# 1A19J6_1A20J15_A.net
KiCad netlist of a schematic drawn in Altium Designer
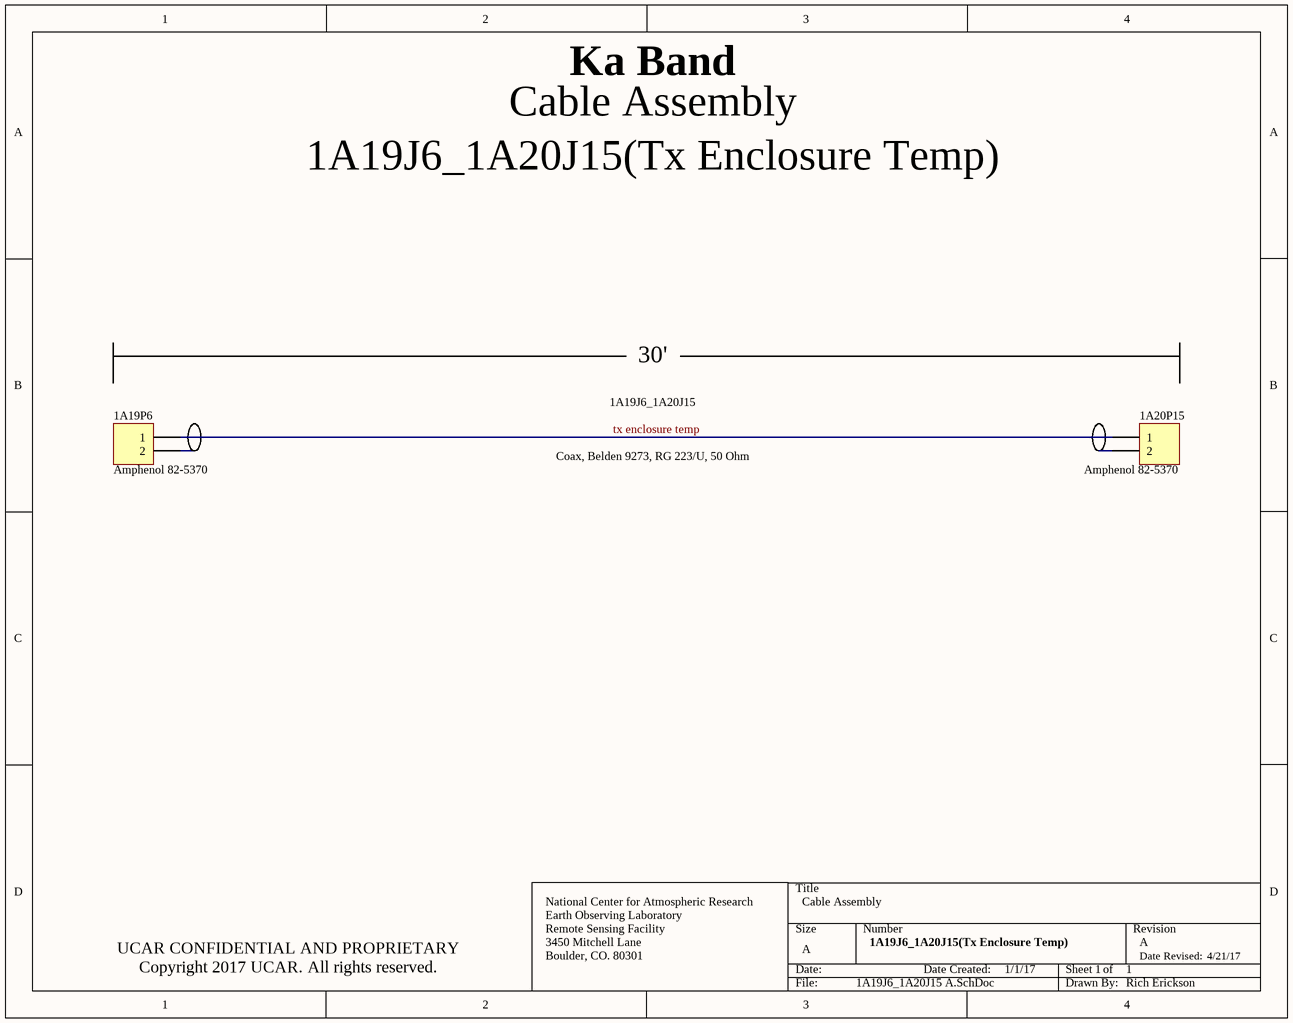
[diagram p0: 1A19J6_1A20J15 A.SchDoc]

(export (version "E")
  (design (tool "Eeschema 10.0.6"))
  (components
    (comp (ref "1A19P6")
      (value "Amphenol 82-5370")
      (footprint "HDR1X2")
      (description "Header, 2-Pin")
      (fields (field (name "PUBLISHER") "Altium Limited"))
      (libsource (lib "") (part "Header 2_1"))
    )
    (comp (ref "1A20P15")
      (value "Amphenol 82-5370")
      (footprint "HDR1X2")
      (description "Header, 2-Pin")
      (fields (field (name "PUBLISHER") "Altium Limited"))
      (libsource (lib "Miscellaneous Connectors") (part "Header 2"))
    )
  )
  (nets
    (net (code "1") (name "/tx enclosure temp") (class "Default")
      (node (ref "1A19P6") (pin "1") (pinfunction "1_1") (pintype "passive"))
      (node (ref "1A20P15") (pin "1") (pinfunction "1_1") (pintype "passive"))
    )
    (net (code "2") (name "unconnected-(1A19P6-Pad2)") (class "Default")
      (node (ref "1A19P6") (pin "2") (pinfunction "2_2") (pintype "passive"))
    )
    (net (code "3") (name "unconnected-(1A20P15-Pad2)") (class "Default")
      (node (ref "1A20P15") (pin "2") (pinfunction "2_2") (pintype "passive"))
    )
  )
)
